# MPPT_Charge_Controller.net
KiCad netlist of a schematic drawn in EAGLE
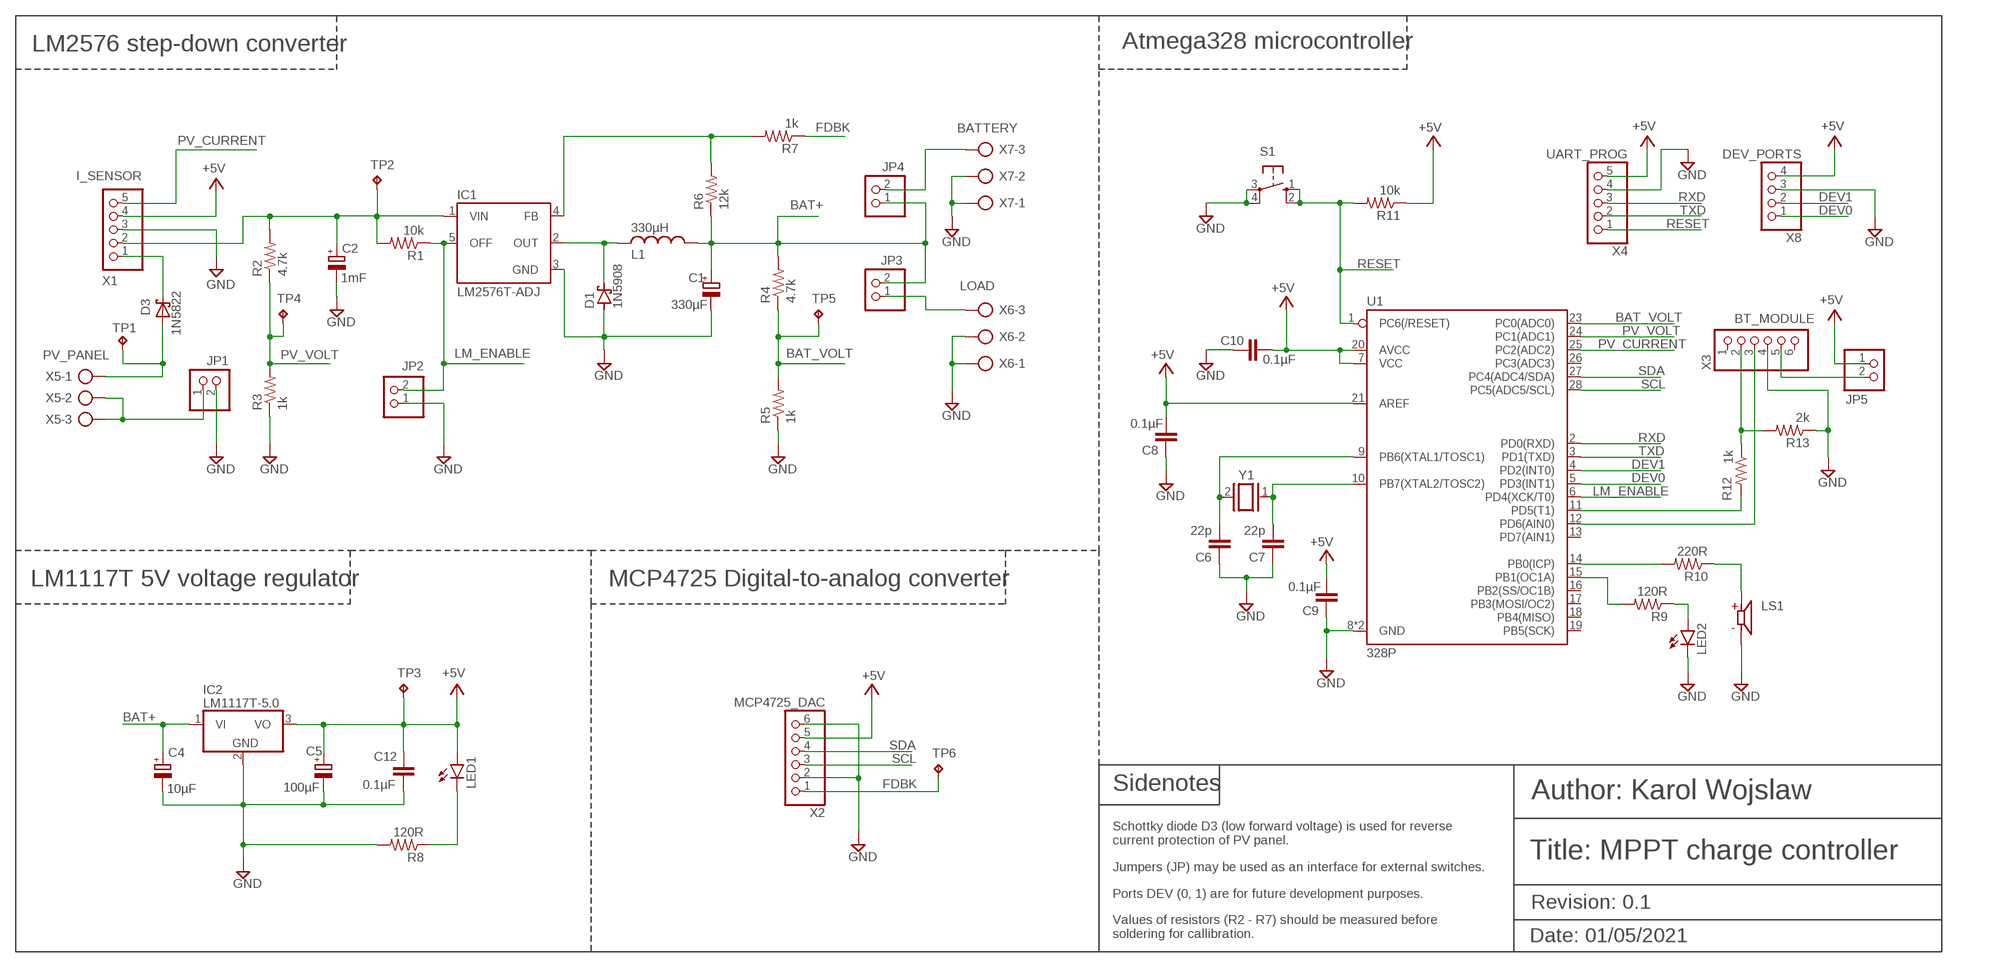
[diagram p0: schematic, sheet 1]

(export (version "E")
  (design (tool "Eeschema 10.0.6"))
  (components
    (comp (ref "C1")
      (value "330µF")
      (footprint "eagle-import:E2-5")
      (libsource (lib "eagle-import") (part "CPOL-EUE2-5"))
    )
    (comp (ref "C2")
      (value "1mF")
      (footprint "eagle-import:E2-5")
      (libsource (lib "eagle-import") (part "CPOL-EUE2-5"))
    )
    (comp (ref "C4")
      (value "10µF")
      (footprint "eagle-import:E2-5")
      (libsource (lib "eagle-import") (part "CPOL-EUE2-5"))
    )
    (comp (ref "C5")
      (value "100µF")
      (footprint "eagle-import:E2-5")
      (libsource (lib "eagle-import") (part "CPOL-EUE2-5"))
    )
    (comp (ref "C6")
      (value "22p")
      (footprint "eagle-import:C025-025X050")
      (libsource (lib "eagle-import") (part "C-EU025-025X050"))
    )
    (comp (ref "C7")
      (value "22p")
      (footprint "eagle-import:C025-025X050")
      (libsource (lib "eagle-import") (part "C-EU025-025X050"))
    )
    (comp (ref "C8")
      (value "0.1µF")
      (footprint "eagle-import:C2.5-2")
      (libsource (lib "eagle-import") (part "C2.5/2"))
    )
    (comp (ref "C9")
      (value "0.1µF")
      (footprint "eagle-import:C025-025X050")
      (libsource (lib "eagle-import") (part "C-EU025-025X050"))
    )
    (comp (ref "C10")
      (value "0.1µF")
      (footprint "eagle-import:C025-025X050")
      (libsource (lib "eagle-import") (part "C-EU025-025X050"))
    )
    (comp (ref "C12")
      (value "0.1µF")
      (footprint "eagle-import:C025-025X050")
      (libsource (lib "eagle-import") (part "C-EU025-025X050"))
    )
    (comp (ref "D1")
      (value "1N5908")
      (footprint "eagle-import:DO201T15")
      (libsource (lib "eagle-import") (part "diode_210_SCHOTTKY-DIODEDO201T15"))
    )
    (comp (ref "D3")
      (value "1N5822")
      (footprint "eagle-import:DO201T15")
      (libsource (lib "eagle-import") (part "SCHOTTKY-DIODEDO201T15"))
    )
    (comp (ref "IC1")
      (value "LM2576T-ADJ")
      (footprint "eagle-import:TO220-5")
      (libsource (lib "eagle-import") (part "LM2576T"))
    )
    (comp (ref "IC2")
      (value "LM1117T-5.0")
      (footprint "eagle-import:TO220V")
      (libsource (lib "eagle-import") (part "78TV05"))
    )
    (comp (ref "JP1")
      (value "PINHD-1X2")
      (footprint "eagle-import:1X02")
      (libsource (lib "eagle-import") (part "PINHD-1X2"))
    )
    (comp (ref "JP2")
      (value "PINHD-1X2")
      (footprint "eagle-import:1X02")
      (libsource (lib "eagle-import") (part "PINHD-1X2"))
    )
    (comp (ref "JP3")
      (value "PINHD-1X2")
      (footprint "eagle-import:1X02")
      (libsource (lib "eagle-import") (part "PINHD-1X2"))
    )
    (comp (ref "JP4")
      (value "PINHD-1X2")
      (footprint "eagle-import:1X02")
      (libsource (lib "eagle-import") (part "PINHD-1X2"))
    )
    (comp (ref "JP5")
      (value "PINHD-1X2")
      (footprint "eagle-import:1X02")
      (libsource (lib "eagle-import") (part "PINHD-1X2"))
    )
    (comp (ref "L1")
      (value "330µH")
      (footprint "eagle-import:6000-XXXX-RC")
      (libsource (lib "eagle-import") (part "L-US6000-XXX-RC"))
    )
    (comp (ref "LED1")
      (value "LED5MM")
      (footprint "eagle-import:LED5MM")
      (libsource (lib "eagle-import") (part "LED5MM"))
    )
    (comp (ref "LED2")
      (value "LED5MM")
      (footprint "eagle-import:LED5MM")
      (libsource (lib "eagle-import") (part "LED5MM"))
    )
    (comp (ref "LS1")
      (value "CEM-1205C")
      (footprint "eagle-import:CUI_CEM-1205C")
      (fields (field (name "MF") "CUI Devices"))
      (libsource (lib "eagle-import") (part "CEM-1205C"))
    )
    (comp (ref "R1")
      (value "10k")
      (footprint "eagle-import:0207_10")
      (libsource (lib "eagle-import") (part "R-US_0207/10"))
    )
    (comp (ref "R2")
      (value "4.7k")
      (footprint "eagle-import:0207_10")
      (libsource (lib "eagle-import") (part "R-US_0207/10"))
    )
    (comp (ref "R3")
      (value "1k")
      (footprint "eagle-import:0207_10")
      (libsource (lib "eagle-import") (part "R-US_0207/10"))
    )
    (comp (ref "R4")
      (value "4.7k")
      (footprint "eagle-import:0207_10")
      (libsource (lib "eagle-import") (part "R-US_0207/10"))
    )
    (comp (ref "R5")
      (value "1k")
      (footprint "eagle-import:0207_10")
      (libsource (lib "eagle-import") (part "R-US_0207/10"))
    )
    (comp (ref "R6")
      (value "12k")
      (footprint "eagle-import:0207_10")
      (libsource (lib "eagle-import") (part "R-US_0207/10"))
    )
    (comp (ref "R7")
      (value "1k")
      (footprint "eagle-import:0207_10")
      (libsource (lib "eagle-import") (part "R-US_0207/10"))
    )
    (comp (ref "R8")
      (value "120R")
      (footprint "eagle-import:0207_10")
      (libsource (lib "eagle-import") (part "R-US_0207/10"))
    )
    (comp (ref "R9")
      (value "120R")
      (footprint "eagle-import:0207_10")
      (libsource (lib "eagle-import") (part "R-US_0207/10"))
    )
    (comp (ref "R10")
      (value "220R")
      (footprint "eagle-import:0207_10")
      (libsource (lib "eagle-import") (part "R-US_0207/10"))
    )
    (comp (ref "R11")
      (value "10k")
      (footprint "eagle-import:0207_10")
      (libsource (lib "eagle-import") (part "R-US_0207/10"))
    )
    (comp (ref "R12")
      (value "1k")
      (footprint "eagle-import:0207_10")
      (libsource (lib "eagle-import") (part "R-US_0207/10"))
    )
    (comp (ref "R13")
      (value "2k")
      (footprint "eagle-import:0207_10")
      (libsource (lib "eagle-import") (part "R-US_0207/10"))
    )
    (comp (ref "S1")
      (value "10-XX")
      (footprint "eagle-import:B3F-10XX")
      (fields (field (name "MPN") "B3F-1000"))
      (libsource (lib "eagle-import") (part "10-XX"))
    )
    (comp (ref "TP1")
      (value "TPPAD1-13")
      (footprint "eagle-import:P1-13")
      (libsource (lib "eagle-import") (part "TPPAD1-13"))
    )
    (comp (ref "TP2")
      (value "TPPAD1-13")
      (footprint "eagle-import:P1-13")
      (libsource (lib "eagle-import") (part "TPPAD1-13"))
    )
    (comp (ref "TP3")
      (value "TPPAD1-13")
      (footprint "eagle-import:P1-13")
      (libsource (lib "eagle-import") (part "TPPAD1-13"))
    )
    (comp (ref "TP4")
      (value "TPPAD1-13")
      (footprint "eagle-import:P1-13")
      (libsource (lib "eagle-import") (part "TPPAD1-13"))
    )
    (comp (ref "TP5")
      (value "TPPAD1-13")
      (footprint "eagle-import:P1-13")
      (libsource (lib "eagle-import") (part "TPPAD1-13"))
    )
    (comp (ref "TP6")
      (value "TPPAD1-13")
      (footprint "eagle-import:P1-13")
      (libsource (lib "eagle-import") (part "TPPAD1-13"))
    )
    (comp (ref "U1")
      (value "328P")
      (footprint "eagle-import:DIP28")
      (libsource (lib "eagle-import") (part "ATMEGA328P_PDIP"))
    )
    (comp (ref "X1")
      (value "I_SENSOR")
      (footprint "eagle-import:1X05")
      (libsource (lib "eagle-import") (part "PINHD-1X5"))
    )
    (comp (ref "X2")
      (value "MCP4725_DAC")
      (footprint "eagle-import:1X06")
      (libsource (lib "eagle-import") (part "PINHD-1X6"))
    )
    (comp (ref "X3")
      (value "BT_MODULE")
      (footprint "eagle-import:1X06")
      (libsource (lib "eagle-import") (part "PINHD-1X6"))
    )
    (comp (ref "X4")
      (value "UART_PROG")
      (footprint "eagle-import:1X05")
      (libsource (lib "eagle-import") (part "PINHD-1X5"))
    )
    (comp (ref "X5")
      (value "PV_PANEL")
      (footprint "eagle-import:AK300_3")
      (libsource (lib "eagle-import") (part "AK300/3"))
    )
    (comp (ref "X6")
      (value "LOAD")
      (footprint "eagle-import:AK500_3")
      (libsource (lib "eagle-import") (part "AK500/3"))
    )
    (comp (ref "X7")
      (value "BATTERY")
      (footprint "eagle-import:AK500_3")
      (libsource (lib "eagle-import") (part "AK500/3"))
    )
    (comp (ref "X8")
      (value "DEV_PORTS")
      (footprint "eagle-import:1X04")
      (libsource (lib "eagle-import") (part "PINHD-1X4"))
    )
    (comp (ref "Y1")
      (value "16MHz")
      (footprint "eagle-import:QS")
      (libsource (lib "eagle-import") (part "XTAL/S"))
    )
  )
  (nets
    (net (code "1") (name "+5V") (class "Default")
      (node (ref "C10") (pin "2") (pinfunction "2_2") (pintype "passive"))
      (node (ref "C12") (pin "2") (pinfunction "2_2") (pintype "passive"))
      (node (ref "C5") (pin "+") (pinfunction "+_+") (pintype "passive"))
      (node (ref "C8") (pin "2") (pinfunction "2_2") (pintype "passive"))
      (node (ref "C9") (pin "2") (pinfunction "2_2") (pintype "passive"))
      (node (ref "IC2") (pin "3") (pinfunction "VO_3") (pintype "passive"))
      (node (ref "JP5") (pin "1") (pinfunction "1_1") (pintype "passive"))
      (node (ref "LED1") (pin "A") (pinfunction "A_A") (pintype "passive"))
      (node (ref "R11") (pin "1") (pinfunction "1_1") (pintype "passive"))
      (node (ref "TP3") (pin "TP") (pinfunction "TP_TP") (pintype "input"))
      (node (ref "U1") (pin "20") (pinfunction "AVCC_20") (pintype "bidirectional"))
      (node (ref "U1") (pin "21") (pinfunction "AREF_21") (pintype "bidirectional"))
      (node (ref "U1") (pin "7") (pinfunction "VCC_7") (pintype "bidirectional"))
      (node (ref "X1") (pin "4") (pinfunction "4_4") (pintype "passive"))
      (node (ref "X2") (pin "5") (pinfunction "5_5") (pintype "passive"))
      (node (ref "X4") (pin "5") (pinfunction "5_5") (pintype "passive"))
      (node (ref "X8") (pin "4") (pinfunction "4_4") (pintype "passive"))
    )
    (net (code "2") (name "/BAT+") (class "Default")
      (node (ref "C1") (pin "+") (pinfunction "+_+") (pintype "passive"))
      (node (ref "C4") (pin "+") (pinfunction "+_+") (pintype "passive"))
      (node (ref "IC2") (pin "1") (pinfunction "VI_1") (pintype "input"))
      (node (ref "JP3") (pin "2") (pinfunction "2_2") (pintype "passive"))
      (node (ref "JP4") (pin "1") (pinfunction "1_1") (pintype "passive"))
      (node (ref "L1") (pin "1") (pinfunction "1_1") (pintype "passive"))
      (node (ref "R4") (pin "2") (pinfunction "2_2") (pintype "passive"))
      (node (ref "R6") (pin "1") (pinfunction "1_1") (pintype "passive"))
    )
    (net (code "3") (name "/BAT_VOLT") (class "Default")
      (node (ref "R4") (pin "1") (pinfunction "1_1") (pintype "passive"))
      (node (ref "R5") (pin "2") (pinfunction "2_2") (pintype "passive"))
      (node (ref "TP5") (pin "TP") (pinfunction "TP_TP") (pintype "input"))
      (node (ref "U1") (pin "23") (pinfunction "PC0(ADC0)_23") (pintype "bidirectional"))
    )
    (net (code "4") (name "/DEV0") (class "Default")
      (node (ref "U1") (pin "5") (pinfunction "PD3(INT1)_5") (pintype "bidirectional"))
      (node (ref "X8") (pin "1") (pinfunction "1_1") (pintype "passive"))
    )
    (net (code "5") (name "/DEV1") (class "Default")
      (node (ref "U1") (pin "4") (pinfunction "PD2(INT0)_4") (pintype "bidirectional"))
      (node (ref "X8") (pin "2") (pinfunction "2_2") (pintype "passive"))
    )
    (net (code "6") (name "/FDBK") (class "Default")
      (node (ref "R7") (pin "1") (pinfunction "1_1") (pintype "passive"))
      (node (ref "TP6") (pin "TP") (pinfunction "TP_TP") (pintype "input"))
      (node (ref "X2") (pin "1") (pinfunction "1_1") (pintype "passive"))
    )
    (net (code "7") (name "/LM_ENABLE") (class "Default")
      (node (ref "IC1") (pin "5") (pinfunction "OFF_5") (pintype "input"))
      (node (ref "JP2") (pin "2") (pinfunction "2_2") (pintype "passive"))
      (node (ref "R1") (pin "1") (pinfunction "1_1") (pintype "passive"))
      (node (ref "U1") (pin "6") (pinfunction "PD4(XCK/T0)_6") (pintype "bidirectional"))
    )
    (net (code "8") (name "/PV_CURRENT") (class "Default")
      (node (ref "U1") (pin "25") (pinfunction "PC2(ADC2)_25") (pintype "bidirectional"))
      (node (ref "X1") (pin "5") (pinfunction "5_5") (pintype "passive"))
    )
    (net (code "9") (name "/PV_VOLT") (class "Default")
      (node (ref "R2") (pin "1") (pinfunction "1_1") (pintype "passive"))
      (node (ref "R3") (pin "2") (pinfunction "2_2") (pintype "passive"))
      (node (ref "TP4") (pin "TP") (pinfunction "TP_TP") (pintype "input"))
      (node (ref "U1") (pin "24") (pinfunction "PC1(ADC1)_24") (pintype "bidirectional"))
    )
    (net (code "10") (name "/RESET") (class "Default")
      (node (ref "R11") (pin "2") (pinfunction "2_2") (pintype "passive"))
      (node (ref "S1") (pin "1") (pinfunction "S_1") (pintype "passive"))
      (node (ref "S1") (pin "2") (pinfunction "S1_2") (pintype "passive"))
      (node (ref "U1") (pin "1") (pinfunction "PC6(/RESET)_1") (pintype "bidirectional"))
      (node (ref "X4") (pin "1") (pinfunction "1_1") (pintype "passive"))
    )
    (net (code "11") (name "/RXD") (class "Default")
      (node (ref "U1") (pin "2") (pinfunction "PD0(RXD)_2") (pintype "bidirectional"))
      (node (ref "X4") (pin "3") (pinfunction "3_3") (pintype "passive"))
    )
    (net (code "12") (name "/SCL") (class "Default")
      (node (ref "U1") (pin "28") (pinfunction "PC5(ADC5/SCL)_28") (pintype "bidirectional"))
      (node (ref "X2") (pin "3") (pinfunction "3_3") (pintype "passive"))
    )
    (net (code "13") (name "/SDA") (class "Default")
      (node (ref "U1") (pin "27") (pinfunction "PC4(ADC4/SDA)_27") (pintype "bidirectional"))
      (node (ref "X2") (pin "4") (pinfunction "4_4") (pintype "passive"))
    )
    (net (code "14") (name "/TXD") (class "Default")
      (node (ref "U1") (pin "3") (pinfunction "PD1(TXD)_3") (pintype "bidirectional"))
      (node (ref "X4") (pin "2") (pinfunction "2_2") (pintype "passive"))
    )
    (net (code "15") (name "GND") (class "Default")
      (node (ref "C1") (pin "-") (pinfunction "-_-") (pintype "passive"))
      (node (ref "C10") (pin "1") (pinfunction "1_1") (pintype "passive"))
      (node (ref "C12") (pin "1") (pinfunction "1_1") (pintype "passive"))
      (node (ref "C2") (pin "-") (pinfunction "-_-") (pintype "passive"))
      (node (ref "C4") (pin "-") (pinfunction "-_-") (pintype "passive"))
      (node (ref "C5") (pin "-") (pinfunction "-_-") (pintype "passive"))
      (node (ref "C6") (pin "1") (pinfunction "1_1") (pintype "passive"))
      (node (ref "C7") (pin "1") (pinfunction "1_1") (pintype "passive"))
      (node (ref "C8") (pin "1") (pinfunction "1_1") (pintype "passive"))
      (node (ref "C9") (pin "1") (pinfunction "1_1") (pintype "passive"))
      (node (ref "D1") (pin "A") (pinfunction "A_A") (pintype "passive"))
      (node (ref "IC1") (pin "3") (pinfunction "GND_3") (pintype "power_in"))
      (node (ref "IC2") (pin "2") (pinfunction "GND_2") (pintype "passive"))
      (node (ref "JP1") (pin "2") (pinfunction "2_2") (pintype "passive"))
      (node (ref "JP2") (pin "1") (pinfunction "1_1") (pintype "passive"))
      (node (ref "LED2") (pin "K") (pinfunction "C_K") (pintype "passive"))
      (node (ref "LS1") (pin "N") (pinfunction "N_N") (pintype "passive"))
      (node (ref "R13") (pin "1") (pinfunction "1_1") (pintype "passive"))
      (node (ref "R3") (pin "1") (pinfunction "1_1") (pintype "passive"))
      (node (ref "R5") (pin "1") (pinfunction "1_1") (pintype "passive"))
      (node (ref "R8") (pin "2") (pinfunction "2_2") (pintype "passive"))
      (node (ref "S1") (pin "3") (pinfunction "P_3") (pintype "passive"))
      (node (ref "S1") (pin "4") (pinfunction "P1_4") (pintype "passive"))
      (node (ref "U1") (pin "22") (pinfunction "GND_22") (pintype "bidirectional"))
      (node (ref "U1") (pin "8") (pinfunction "GND_8") (pintype "bidirectional"))
      (node (ref "X1") (pin "3") (pinfunction "3_3") (pintype "passive"))
      (node (ref "X2") (pin "2") (pinfunction "2_2") (pintype "passive"))
      (node (ref "X2") (pin "6") (pinfunction "6_6") (pintype "passive"))
      (node (ref "X3") (pin "4") (pinfunction "4_4") (pintype "passive"))
      (node (ref "X4") (pin "4") (pinfunction "4_4") (pintype "passive"))
      (node (ref "X6") (pin "1") (pinfunction "KL_1") (pintype "passive"))
      (node (ref "X6") (pin "2") (pinfunction "KL_2") (pintype "passive"))
      (node (ref "X7") (pin "1") (pinfunction "KL_1") (pintype "passive"))
      (node (ref "X7") (pin "2") (pinfunction "KL_2") (pintype "passive"))
      (node (ref "X8") (pin "3") (pinfunction "3_3") (pintype "passive"))
    )
    (net (code "16") (name "Net-(D3-PadC)") (class "Default")
      (node (ref "D3") (pin "C") (pinfunction "C_C") (pintype "passive"))
      (node (ref "X1") (pin "1") (pinfunction "1_1") (pintype "passive"))
    )
    (net (code "17") (name "Net-(IC1-FB)") (class "Default")
      (node (ref "IC1") (pin "4") (pinfunction "FB_4") (pintype "input"))
      (node (ref "R6") (pin "2") (pinfunction "2_2") (pintype "passive"))
      (node (ref "R7") (pin "2") (pinfunction "2_2") (pintype "passive"))
    )
    (net (code "18") (name "Net-(IC1-OUT)") (class "Default")
      (node (ref "D1") (pin "C") (pinfunction "C_C") (pintype "passive"))
      (node (ref "IC1") (pin "2") (pinfunction "OUT_2") (pintype "output"))
      (node (ref "L1") (pin "2") (pinfunction "2_2") (pintype "passive"))
    )
    (net (code "19") (name "Net-(IC1-VIN)") (class "Default")
      (node (ref "C2") (pin "+") (pinfunction "+_+") (pintype "passive"))
      (node (ref "IC1") (pin "1") (pinfunction "VIN_1") (pintype "power_in"))
      (node (ref "R1") (pin "2") (pinfunction "2_2") (pintype "passive"))
      (node (ref "R2") (pin "2") (pinfunction "2_2") (pintype "passive"))
      (node (ref "TP2") (pin "TP") (pinfunction "TP_TP") (pintype "input"))
      (node (ref "X1") (pin "2") (pinfunction "2_2") (pintype "passive"))
    )
    (net (code "20") (name "Net-(JP5-Pad2)") (class "Default")
      (node (ref "JP5") (pin "2") (pinfunction "2_2") (pintype "passive"))
      (node (ref "X3") (pin "5") (pinfunction "5_5") (pintype "passive"))
    )
    (net (code "21") (name "Net-(LED1-C)") (class "Default")
      (node (ref "LED1") (pin "K") (pinfunction "C_K") (pintype "passive"))
      (node (ref "R8") (pin "1") (pinfunction "1_1") (pintype "passive"))
    )
    (net (code "22") (name "Net-(LED2-PadA)") (class "Default")
      (node (ref "LED2") (pin "A") (pinfunction "A_A") (pintype "passive"))
      (node (ref "R9") (pin "1") (pinfunction "1_1") (pintype "passive"))
    )
    (net (code "23") (name "Net-(LS1-PadP)") (class "Default")
      (node (ref "LS1") (pin "P") (pinfunction "P_P") (pintype "passive"))
      (node (ref "R10") (pin "1") (pinfunction "1_1") (pintype "passive"))
    )
    (net (code "24") (name "Net-(R12-Pad1)") (class "Default")
      (node (ref "R12") (pin "1") (pinfunction "1_1") (pintype "passive"))
      (node (ref "R13") (pin "2") (pinfunction "2_2") (pintype "passive"))
      (node (ref "X3") (pin "2") (pinfunction "2_2") (pintype "passive"))
    )
    (net (code "25") (name "Net-(U1-PB0(ICP))") (class "Default")
      (node (ref "R10") (pin "2") (pinfunction "2_2") (pintype "passive"))
      (node (ref "U1") (pin "14") (pinfunction "PB0(ICP)_14") (pintype "bidirectional"))
    )
    (net (code "26") (name "Net-(U1-PB1(OC1A))") (class "Default")
      (node (ref "R9") (pin "2") (pinfunction "2_2") (pintype "passive"))
      (node (ref "U1") (pin "15") (pinfunction "PB1(OC1A)_15") (pintype "bidirectional"))
    )
    (net (code "27") (name "Net-(U1-PB6(XTAL1{slash}TOSC1))") (class "Default")
      (node (ref "C6") (pin "2") (pinfunction "2_2") (pintype "passive"))
      (node (ref "U1") (pin "9") (pinfunction "PB6(XTAL1/TOSC1)_9") (pintype "bidirectional"))
      (node (ref "Y1") (pin "2") (pinfunction "2_2") (pintype "passive"))
    )
    (net (code "28") (name "Net-(U1-PB7(XTAL2{slash}TOSC2))") (class "Default")
      (node (ref "C7") (pin "2") (pinfunction "2_2") (pintype "passive"))
      (node (ref "U1") (pin "10") (pinfunction "PB7(XTAL2/TOSC2)_10") (pintype "bidirectional"))
      (node (ref "Y1") (pin "1") (pinfunction "1_1") (pintype "passive"))
    )
    (net (code "29") (name "Net-(U1-PD5(T1))") (class "Default")
      (node (ref "R12") (pin "2") (pinfunction "2_2") (pintype "passive"))
      (node (ref "U1") (pin "11") (pinfunction "PD5(T1)_11") (pintype "bidirectional"))
    )
    (net (code "30") (name "Net-(U1-PD6(AIN0))") (class "Default")
      (node (ref "U1") (pin "12") (pinfunction "PD6(AIN0)_12") (pintype "bidirectional"))
      (node (ref "X3") (pin "3") (pinfunction "3_3") (pintype "passive"))
    )
    (net (code "31") (name "Net-(X5A-KL)") (class "Default")
      (node (ref "D3") (pin "A") (pinfunction "A_A") (pintype "passive"))
      (node (ref "TP1") (pin "TP") (pinfunction "TP_TP") (pintype "input"))
      (node (ref "X5") (pin "1") (pinfunction "KL_1") (pintype "passive"))
    )
    (net (code "32") (name "Net-(X5B-KL)") (class "Default")
      (node (ref "JP1") (pin "1") (pinfunction "1_1") (pintype "passive"))
      (node (ref "X5") (pin "2") (pinfunction "KL_2") (pintype "passive"))
      (node (ref "X5") (pin "3") (pinfunction "KL_3") (pintype "passive"))
    )
    (net (code "33") (name "Net-(X6C-KL)") (class "Default")
      (node (ref "JP3") (pin "1") (pinfunction "1_1") (pintype "passive"))
      (node (ref "X6") (pin "3") (pinfunction "KL_3") (pintype "passive"))
    )
    (net (code "34") (name "Net-(X7C-KL)") (class "Default")
      (node (ref "JP4") (pin "2") (pinfunction "2_2") (pintype "passive"))
      (node (ref "X7") (pin "3") (pinfunction "KL_3") (pintype "passive"))
    )
    (net (code "35") (name "unconnected-(U1-PB2(SS{slash}OC1B)-Pad16)") (class "Default")
      (node (ref "U1") (pin "16") (pinfunction "PB2(SS/OC1B)_16") (pintype "bidirectional"))
    )
    (net (code "36") (name "unconnected-(U1-PB3(MOSI{slash}OC2)-Pad17)") (class "Default")
      (node (ref "U1") (pin "17") (pinfunction "PB3(MOSI/OC2)_17") (pintype "bidirectional"))
    )
    (net (code "37") (name "unconnected-(U1-PB4(MISO)-Pad18)") (class "Default")
      (node (ref "U1") (pin "18") (pinfunction "PB4(MISO)_18") (pintype "bidirectional"))
    )
    (net (code "38") (name "unconnected-(U1-PB5(SCK)-Pad19)") (class "Default")
      (node (ref "U1") (pin "19") (pinfunction "PB5(SCK)_19") (pintype "bidirectional"))
    )
    (net (code "39") (name "unconnected-(U1-PC3(ADC3)-Pad26)") (class "Default")
      (node (ref "U1") (pin "26") (pinfunction "PC3(ADC3)_26") (pintype "bidirectional"))
    )
    (net (code "40") (name "unconnected-(U1-PD7(AIN1)-Pad13)") (class "Default")
      (node (ref "U1") (pin "13") (pinfunction "PD7(AIN1)_13") (pintype "bidirectional"))
    )
    (net (code "41") (name "unconnected-(X3-Pad1)") (class "Default")
      (node (ref "X3") (pin "1") (pinfunction "1_1") (pintype "passive"))
    )
    (net (code "42") (name "unconnected-(X3-Pad6)") (class "Default")
      (node (ref "X3") (pin "6") (pinfunction "6_6") (pintype "passive"))
    )
  )
)
